# FM.net
KiCad netlist of a schematic drawn in Altium Designer
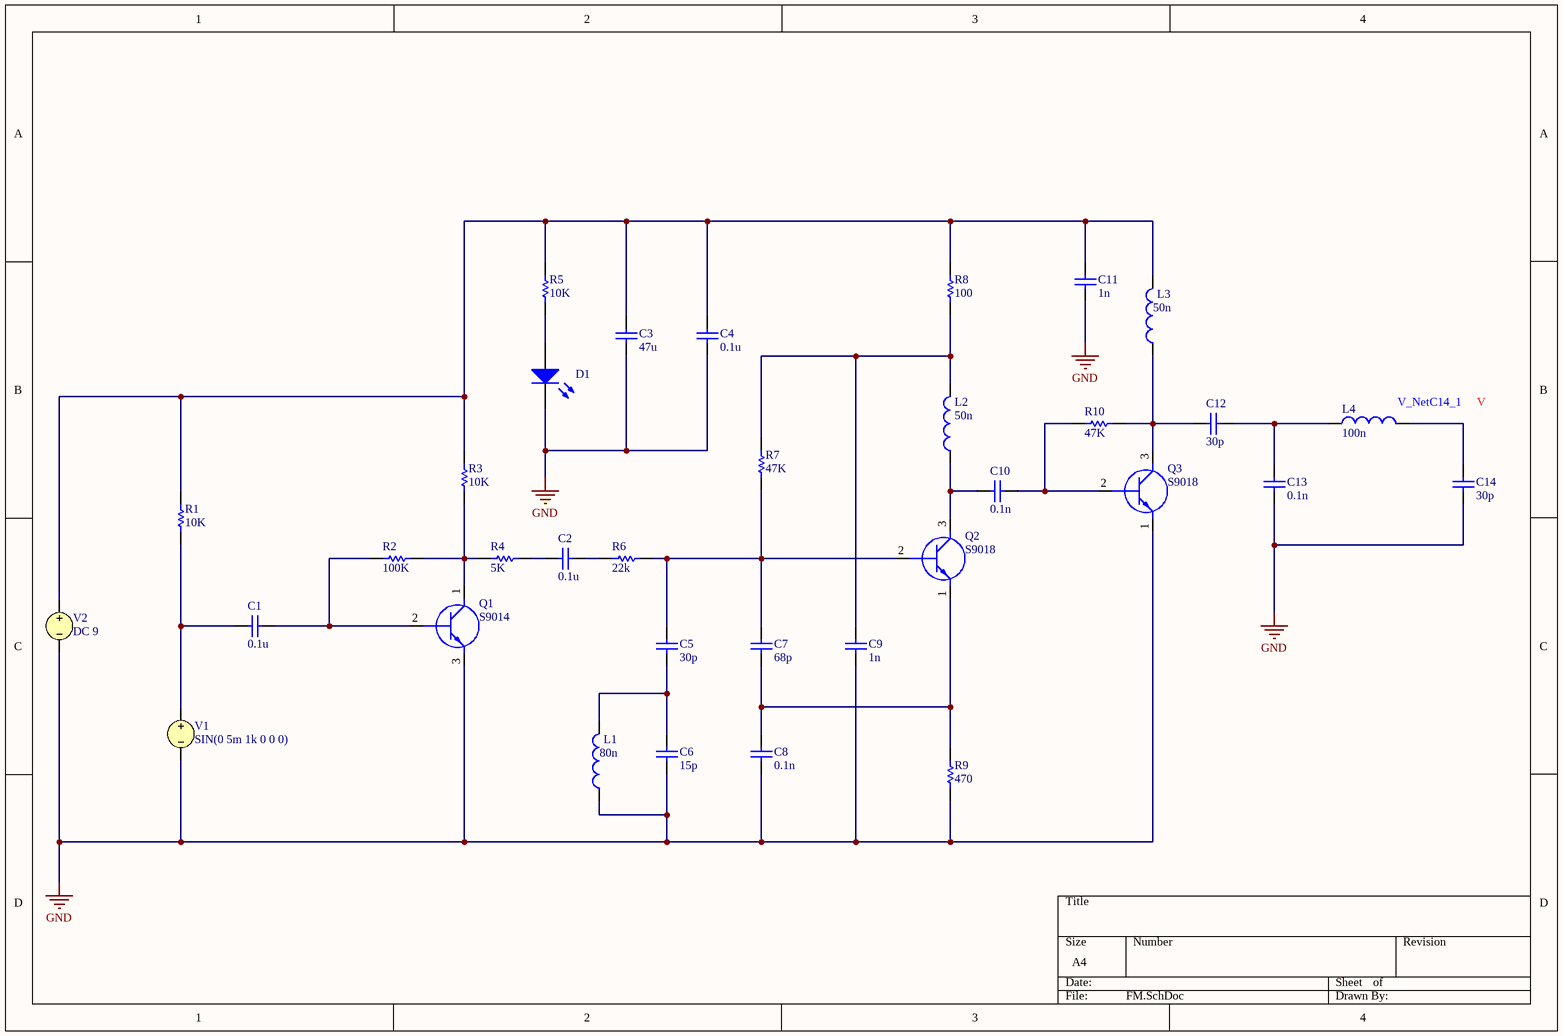
[diagram p0: FM.SchDoc]

(export (version "E")
  (design (tool "Eeschema 10.0.6"))
  (components
    (comp (ref "C1")
      (value "0.1u")
      (description "Capacitor")
      (libsource (lib "Simulation Generic Components") (part "Capacitor"))
    )
    (comp (ref "C2")
      (value "0.1u")
      (description "Capacitor")
      (libsource (lib "Simulation Generic Components") (part "Capacitor"))
    )
    (comp (ref "C3")
      (value "47u")
      (description "Capacitor")
      (libsource (lib "Simulation Generic Components") (part "Capacitor"))
    )
    (comp (ref "C4")
      (value "0.1u")
      (description "Capacitor")
      (libsource (lib "Simulation Generic Components") (part "Capacitor"))
    )
    (comp (ref "C5")
      (value "30p")
      (description "Capacitor")
      (libsource (lib "Simulation Generic Components") (part "Capacitor"))
    )
    (comp (ref "C6")
      (value "15p")
      (description "Capacitor")
      (libsource (lib "Simulation Generic Components") (part "Capacitor"))
    )
    (comp (ref "C7")
      (value "68p")
      (description "Capacitor")
      (libsource (lib "Simulation Generic Components") (part "Capacitor"))
    )
    (comp (ref "C8")
      (value "0.1n")
      (description "Capacitor")
      (libsource (lib "Simulation Generic Components") (part "Capacitor"))
    )
    (comp (ref "C9")
      (value "1n")
      (description "Capacitor")
      (libsource (lib "Simulation Generic Components") (part "Capacitor"))
    )
    (comp (ref "C10")
      (value "0.1n")
      (description "Capacitor")
      (libsource (lib "Simulation Generic Components") (part "Capacitor"))
    )
    (comp (ref "C11")
      (value "1n")
      (description "Capacitor")
      (libsource (lib "Simulation Generic Components") (part "Capacitor"))
    )
    (comp (ref "C12")
      (value "30p")
      (description "Capacitor")
      (libsource (lib "Simulation Generic Components") (part "Capacitor"))
    )
    (comp (ref "C13")
      (value "0.1n")
      (description "Capacitor")
      (libsource (lib "Simulation Generic Components") (part "Capacitor"))
    )
    (comp (ref "C14")
      (value "30p")
      (description "Capacitor")
      (libsource (lib "Simulation Generic Components") (part "Capacitor"))
    )
    (comp (ref "D1")
      (value "Light-Emitting Diode")
      (libsource (lib "Simulation Generic Components") (part "LED"))
    )
    (comp (ref "L1")
      (value "80n")
      (description "Inductor")
      (libsource (lib "Simulation Generic Components") (part "Inductor"))
    )
    (comp (ref "L2")
      (value "50n")
      (description "Inductor")
      (libsource (lib "Simulation Generic Components") (part "Inductor"))
    )
    (comp (ref "L3")
      (value "50n")
      (description "Inductor")
      (libsource (lib "Simulation Generic Components") (part "Inductor"))
    )
    (comp (ref "L4")
      (value "100n")
      (description "Inductor")
      (libsource (lib "Simulation Generic Components") (part "Inductor"))
    )
    (comp (ref "Q1")
      (value "S9014")
      (footprint "SamacSys:S9014")
      (description "Transistor BJT NPN")
      (libsource (lib "*") (part "S9014"))
    )
    (comp (ref "Q2")
      (value "S9018")
      (footprint "SamacSys:S9018")
      (description "Transistor BJT NPN")
      (libsource (lib "*") (part "S9018"))
    )
    (comp (ref "Q3")
      (value "S9018")
      (footprint "SamacSys:S9018")
      (description "Transistor BJT NPN")
      (libsource (lib "*") (part "S9018"))
    )
    (comp (ref "R1")
      (value "10K")
      (description "Resistor")
      (libsource (lib "Simulation Generic Components") (part "Resistor"))
    )
    (comp (ref "R2")
      (value "100K")
      (description "Resistor")
      (libsource (lib "Simulation Generic Components") (part "Resistor"))
    )
    (comp (ref "R3")
      (value "10K")
      (description "Resistor")
      (libsource (lib "Simulation Generic Components") (part "Resistor"))
    )
    (comp (ref "R4")
      (value "5K")
      (description "Resistor")
      (libsource (lib "Simulation Generic Components") (part "Resistor"))
    )
    (comp (ref "R5")
      (value "10K")
      (description "Resistor")
      (libsource (lib "Simulation Generic Components") (part "Resistor"))
    )
    (comp (ref "R6")
      (value "22k")
      (description "Resistor")
      (libsource (lib "Simulation Generic Components") (part "Resistor"))
    )
    (comp (ref "R7")
      (value "47K")
      (description "Resistor")
      (libsource (lib "Simulation Generic Components") (part "Resistor"))
    )
    (comp (ref "R8")
      (value "100")
      (description "Resistor")
      (libsource (lib "Simulation Generic Components") (part "Resistor"))
    )
    (comp (ref "R9")
      (value "470")
      (description "Resistor")
      (libsource (lib "Simulation Generic Components") (part "Resistor"))
    )
    (comp (ref "R10")
      (value "47K")
      (description "Resistor")
      (libsource (lib "Simulation Generic Components") (part "Resistor"))
    )
    (comp (ref "V1")
      (value "SIN(0 5m 1k 0 0 0)")
      (description "Voltage Source")
      (fields (field (name "PUBLISHER") "Altium Limited"))
      (libsource (lib "Simulation Generic Components") (part "VSRC"))
    )
    (comp (ref "V2")
      (value "DC 9")
      (description "Voltage Source")
      (fields (field (name "PUBLISHER") "Altium Limited"))
      (libsource (lib "Simulation Generic Components") (part "VSRC"))
    )
  )
  (nets
    (net (code "1") (name "GND") (class "Default")
      (node (ref "C11") (pin "1") (pinfunction "1_1") (pintype "passive"))
      (node (ref "C13") (pin "2") (pinfunction "2_2") (pintype "passive"))
      (node (ref "C14") (pin "2") (pinfunction "2_2") (pintype "passive"))
      (node (ref "C3") (pin "1") (pinfunction "1_1") (pintype "passive"))
      (node (ref "C4") (pin "1") (pinfunction "1_1") (pintype "passive"))
      (node (ref "C6") (pin "1") (pinfunction "1_1") (pintype "passive"))
      (node (ref "C8") (pin "1") (pinfunction "1_1") (pintype "passive"))
      (node (ref "C9") (pin "1") (pinfunction "1_1") (pintype "passive"))
      (node (ref "D1") (pin "2") (pinfunction "K_2") (pintype "passive"))
      (node (ref "L1") (pin "1") (pinfunction "1_1") (pintype "passive"))
      (node (ref "Q1") (pin "3") (pinfunction "E_3") (pintype "passive"))
      (node (ref "Q3") (pin "1") (pinfunction "E_1") (pintype "passive"))
      (node (ref "R9") (pin "2") (pinfunction "2_2") (pintype "passive"))
      (node (ref "V1") (pin "2") (pinfunction "2_2") (pintype "passive"))
      (node (ref "V2") (pin "2") (pinfunction "2_2") (pintype "passive"))
    )
    (net (code "2") (name "Net-(C1-Pad1)") (class "Default")
      (node (ref "C1") (pin "1") (pinfunction "1_1") (pintype "passive"))
      (node (ref "R1") (pin "1") (pinfunction "1_1") (pintype "passive"))
      (node (ref "V1") (pin "1") (pinfunction "1_1") (pintype "passive"))
    )
    (net (code "3") (name "Net-(C2-Pad1)") (class "Default")
      (node (ref "C2") (pin "1") (pinfunction "1_1") (pintype "passive"))
      (node (ref "R4") (pin "1") (pinfunction "1_1") (pintype "passive"))
    )
    (net (code "4") (name "Net-(C2-Pad2)") (class "Default")
      (node (ref "C2") (pin "2") (pinfunction "2_2") (pintype "passive"))
      (node (ref "R6") (pin "2") (pinfunction "2_2") (pintype "passive"))
    )
    (net (code "5") (name "Net-(C5-Pad1)") (class "Default")
      (node (ref "C5") (pin "1") (pinfunction "1_1") (pintype "passive"))
      (node (ref "C6") (pin "2") (pinfunction "2_2") (pintype "passive"))
      (node (ref "L1") (pin "2") (pinfunction "2_2") (pintype "passive"))
    )
    (net (code "6") (name "Net-(C9-Pad2)") (class "Default")
      (node (ref "C9") (pin "2") (pinfunction "2_2") (pintype "passive"))
      (node (ref "L2") (pin "2") (pinfunction "2_2") (pintype "passive"))
      (node (ref "R7") (pin "1") (pinfunction "1_1") (pintype "passive"))
      (node (ref "R8") (pin "2") (pinfunction "2_2") (pintype "passive"))
    )
    (net (code "7") (name "Net-(C11-Pad2)") (class "Default")
      (node (ref "C11") (pin "2") (pinfunction "2_2") (pintype "passive"))
      (node (ref "C3") (pin "2") (pinfunction "2_2") (pintype "passive"))
      (node (ref "C4") (pin "2") (pinfunction "2_2") (pintype "passive"))
      (node (ref "L3") (pin "2") (pinfunction "2_2") (pintype "passive"))
      (node (ref "R1") (pin "2") (pinfunction "2_2") (pintype "passive"))
      (node (ref "R3") (pin "2") (pinfunction "2_2") (pintype "passive"))
      (node (ref "R5") (pin "1") (pinfunction "1_1") (pintype "passive"))
      (node (ref "R8") (pin "1") (pinfunction "1_1") (pintype "passive"))
      (node (ref "V2") (pin "1") (pinfunction "1_1") (pintype "passive"))
    )
    (net (code "8") (name "Net-(C12-Pad1)") (class "Default")
      (node (ref "C12") (pin "1") (pinfunction "1_1") (pintype "passive"))
      (node (ref "C13") (pin "1") (pinfunction "1_1") (pintype "passive"))
      (node (ref "L4") (pin "1") (pinfunction "1_1") (pintype "passive"))
    )
    (net (code "9") (name "Net-(C14-Pad1)") (class "Default")
      (node (ref "C14") (pin "1") (pinfunction "1_1") (pintype "passive"))
      (node (ref "L4") (pin "2") (pinfunction "2_2") (pintype "passive"))
    )
    (net (code "10") (name "Net-(D1-A)") (class "Default")
      (node (ref "D1") (pin "1") (pinfunction "A_1") (pintype "passive"))
      (node (ref "R5") (pin "2") (pinfunction "2_2") (pintype "passive"))
    )
    (net (code "11") (name "Net-(Q1-B)") (class "Default")
      (node (ref "C1") (pin "2") (pinfunction "2_2") (pintype "passive"))
      (node (ref "Q1") (pin "2") (pinfunction "B_2") (pintype "passive"))
      (node (ref "R2") (pin "1") (pinfunction "1_1") (pintype "passive"))
    )
    (net (code "12") (name "Net-(Q1-C)") (class "Default")
      (node (ref "Q1") (pin "1") (pinfunction "C_1") (pintype "passive"))
      (node (ref "R2") (pin "2") (pinfunction "2_2") (pintype "passive"))
      (node (ref "R3") (pin "1") (pinfunction "1_1") (pintype "passive"))
      (node (ref "R4") (pin "2") (pinfunction "2_2") (pintype "passive"))
    )
    (net (code "13") (name "Net-(Q2-B)") (class "Default")
      (node (ref "C5") (pin "2") (pinfunction "2_2") (pintype "passive"))
      (node (ref "C7") (pin "2") (pinfunction "2_2") (pintype "passive"))
      (node (ref "Q2") (pin "2") (pinfunction "B_2") (pintype "passive"))
      (node (ref "R6") (pin "1") (pinfunction "1_1") (pintype "passive"))
      (node (ref "R7") (pin "2") (pinfunction "2_2") (pintype "passive"))
    )
    (net (code "14") (name "Net-(Q2-C)") (class "Default")
      (node (ref "C10") (pin "2") (pinfunction "2_2") (pintype "passive"))
      (node (ref "L2") (pin "1") (pinfunction "1_1") (pintype "passive"))
      (node (ref "Q2") (pin "3") (pinfunction "C_3") (pintype "passive"))
    )
    (net (code "15") (name "Net-(Q2-E)") (class "Default")
      (node (ref "C7") (pin "1") (pinfunction "1_1") (pintype "passive"))
      (node (ref "C8") (pin "2") (pinfunction "2_2") (pintype "passive"))
      (node (ref "Q2") (pin "1") (pinfunction "E_1") (pintype "passive"))
      (node (ref "R9") (pin "1") (pinfunction "1_1") (pintype "passive"))
    )
    (net (code "16") (name "Net-(Q3-B)") (class "Default")
      (node (ref "C10") (pin "1") (pinfunction "1_1") (pintype "passive"))
      (node (ref "Q3") (pin "2") (pinfunction "B_2") (pintype "passive"))
      (node (ref "R10") (pin "1") (pinfunction "1_1") (pintype "passive"))
    )
    (net (code "17") (name "Net-(Q3-C)") (class "Default")
      (node (ref "C12") (pin "2") (pinfunction "2_2") (pintype "passive"))
      (node (ref "L3") (pin "1") (pinfunction "1_1") (pintype "passive"))
      (node (ref "Q3") (pin "3") (pinfunction "C_3") (pintype "passive"))
      (node (ref "R10") (pin "2") (pinfunction "2_2") (pintype "passive"))
    )
  )
)
